# sensors.net
KiCad netlist of a schematic drawn in EAGLE
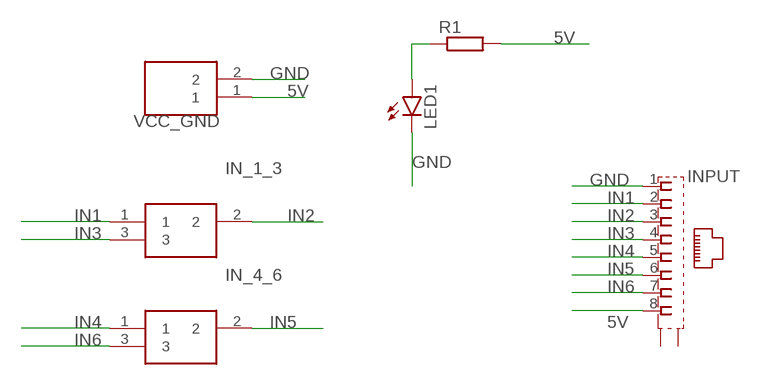
[diagram p0: schematic, sheet 1]

(export (version "E")
  (design (tool "Eeschema 10.0.6"))
  (components
    (comp (ref "INPUT")
      (value "GLX-S-88M")
      (footprint "eagle-import:GLX-S-88M")
      (libsource (lib "eagle-import") (part "GLX-S-88M"))
    )
    (comp (ref "IN_1_3")
      (value "SAMACSYS_PARTS_TB006-508-03BE")
      (footprint "eagle-import:SAMACSYS_PARTS_TB00650803BE")
      (fields
        (field (name "MANUFACTURER_PART_NUMBER") "TB006-508-03BE")
        (field (name "MOUSER_PART_NUMBER") "490-TB006-508-03BE")
      )
      (libsource (lib "eagle-import") (part "SAMACSYS_PARTS_TB006-508-03BE"))
    )
    (comp (ref "IN_4_6")
      (value "SAMACSYS_PARTS_TB006-508-03BE")
      (footprint "eagle-import:SAMACSYS_PARTS_TB00650803BE")
      (fields
        (field (name "MANUFACTURER_PART_NUMBER") "TB006-508-03BE")
        (field (name "MOUSER_PART_NUMBER") "490-TB006-508-03BE")
      )
      (libsource (lib "eagle-import") (part "SAMACSYS_PARTS_TB006-508-03BE"))
    )
    (comp (ref "LED1")
      (value "LED5MM")
      (footprint "eagle-import:LED5MM")
      (libsource (lib "eagle-import") (part "LED5MM"))
    )
    (comp (ref "R1")
      (value "R-EU_0207/10")
      (footprint "eagle-import:0207_10")
      (libsource (lib "eagle-import") (part "R-EU_0207/10"))
    )
    (comp (ref "VCC_GND")
      (value "TB006-508-02BE_TB006-508-02BE")
      (footprint "eagle-import:TB006-508-02BE_CUI_TB006-508-02BE")
      (fields (field (name "MF") "CUI Devices") (field (name "MP") "TB006-508-02BE"))
      (libsource (lib "eagle-import") (part "TB006-508-02BE_TB006-508-02BE"))
    )
  )
  (nets
    (net (code "1") (name "/5V") (class "Default")
      (node (ref "INPUT") (pin "8") (pinfunction "8_8") (pintype "passive"))
      (node (ref "R1") (pin "2") (pinfunction "2_2") (pintype "passive"))
      (node (ref "VCC_GND") (pin "1") (pinfunction "1_1") (pintype "passive"))
    )
    (net (code "2") (name "/GND") (class "Default")
      (node (ref "INPUT") (pin "1") (pinfunction "1_1") (pintype "passive"))
      (node (ref "LED1") (pin "K") (pinfunction "C_K") (pintype "passive"))
      (node (ref "VCC_GND") (pin "2") (pinfunction "2_2") (pintype "passive"))
    )
    (net (code "3") (name "/IN1") (class "Default")
      (node (ref "INPUT") (pin "2") (pinfunction "2_2") (pintype "passive"))
      (node (ref "IN_1_3") (pin "1") (pinfunction "1_1") (pintype "bidirectional"))
    )
    (net (code "4") (name "/IN2") (class "Default")
      (node (ref "INPUT") (pin "3") (pinfunction "3_3") (pintype "passive"))
      (node (ref "IN_1_3") (pin "2") (pinfunction "2_2") (pintype "bidirectional"))
    )
    (net (code "5") (name "/IN3") (class "Default")
      (node (ref "INPUT") (pin "4") (pinfunction "4_4") (pintype "passive"))
      (node (ref "IN_1_3") (pin "3") (pinfunction "3_3") (pintype "bidirectional"))
    )
    (net (code "6") (name "/IN4") (class "Default")
      (node (ref "INPUT") (pin "5") (pinfunction "5_5") (pintype "passive"))
      (node (ref "IN_4_6") (pin "1") (pinfunction "1_1") (pintype "bidirectional"))
    )
    (net (code "7") (name "/IN5") (class "Default")
      (node (ref "INPUT") (pin "6") (pinfunction "6_6") (pintype "passive"))
      (node (ref "IN_4_6") (pin "2") (pinfunction "2_2") (pintype "bidirectional"))
    )
    (net (code "8") (name "/IN6") (class "Default")
      (node (ref "INPUT") (pin "7") (pinfunction "7_7") (pintype "passive"))
      (node (ref "IN_4_6") (pin "3") (pinfunction "3_3") (pintype "bidirectional"))
    )
    (net (code "9") (name "Net-(LED1-PadA)") (class "Default")
      (node (ref "LED1") (pin "A") (pinfunction "A_A") (pintype "passive"))
      (node (ref "R1") (pin "1") (pinfunction "1_1") (pintype "passive"))
    )
    (net (code "10") (name "unconnected-(INPUT-PadS1)") (class "Default")
      (node (ref "INPUT") (pin "S1") (pinfunction "S1_S1") (pintype "passive"))
    )
    (net (code "11") (name "unconnected-(INPUT-PadS2)") (class "Default")
      (node (ref "INPUT") (pin "S2") (pinfunction "S2_S2") (pintype "passive"))
    )
  )
)
